# switchBoardMWS-v1.net
KiCad netlist of a schematic drawn in EAGLE
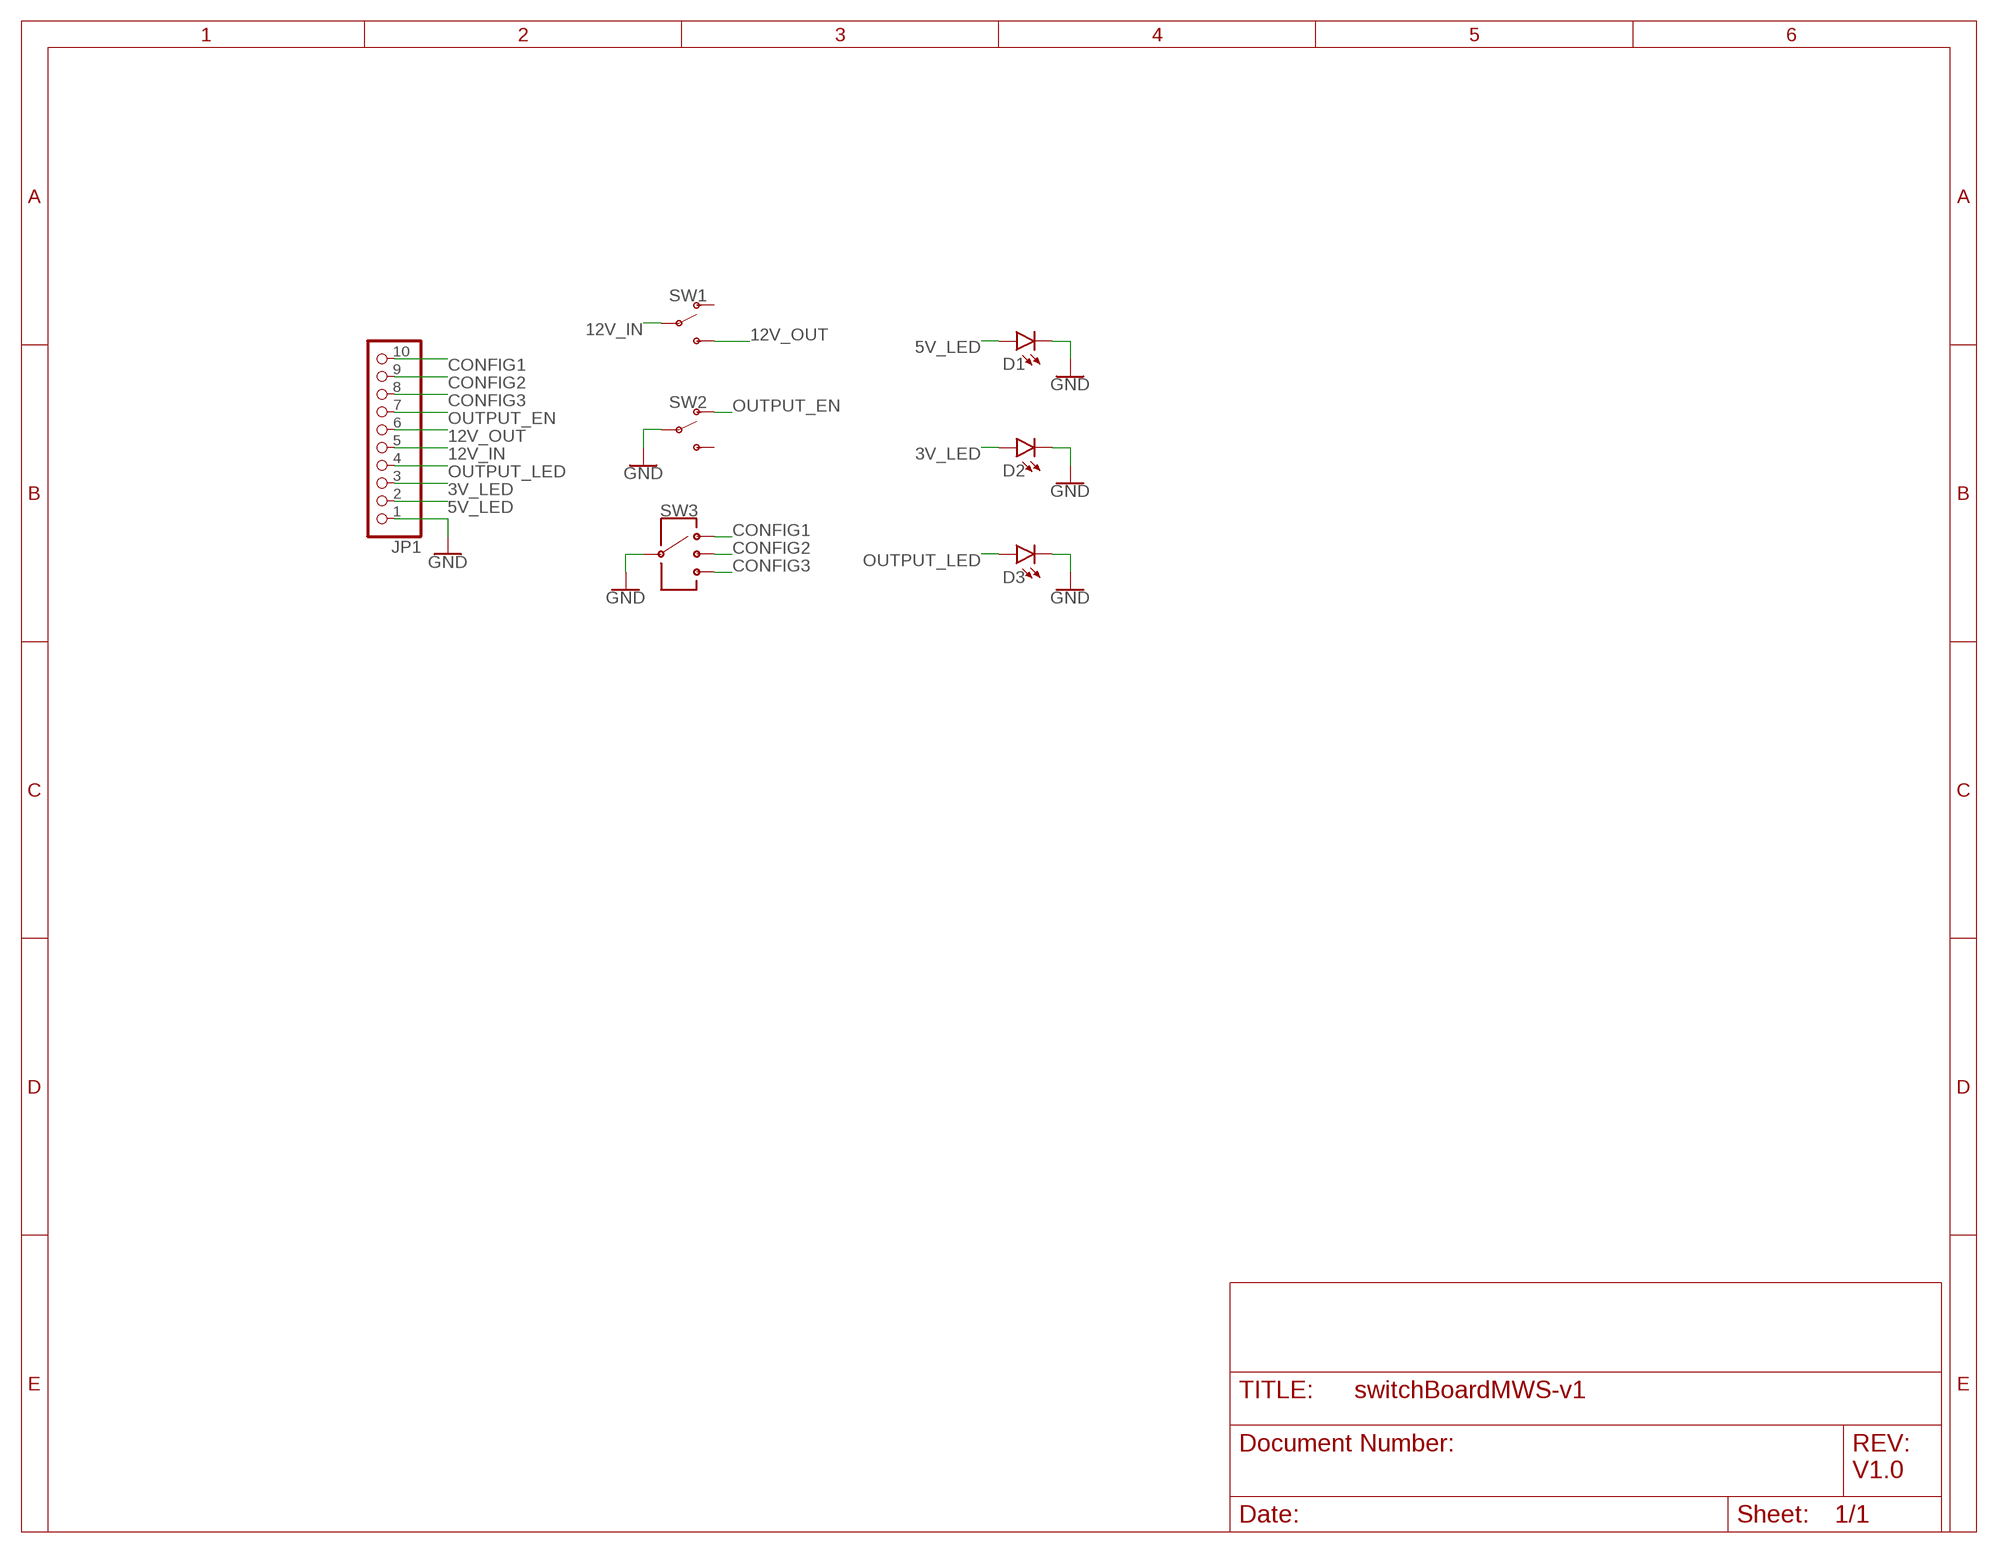
[diagram p0: schematic, sheet 1]

(export (version "E")
  (design (tool "Eeschema 10.0.6"))
  (components
    (comp (ref "D1")
      (value "LED5MM")
      (footprint "eagle-import:LED_5MM")
      (libsource (lib "eagle-import") (part "LED5MM"))
    )
    (comp (ref "D2")
      (value "LED5MM")
      (footprint "eagle-import:LED_5MM")
      (libsource (lib "eagle-import") (part "LED5MM"))
    )
    (comp (ref "D3")
      (value "LED5MM")
      (footprint "eagle-import:LED_5MM")
      (libsource (lib "eagle-import") (part "LED5MM"))
    )
    (comp (ref "JP1")
      (value "PINHD-1X10")
      (footprint "eagle-import:1X10")
      (libsource (lib "eagle-import") (part "PINHD-1X10"))
    )
    (comp (ref "SW1")
      (value "SPDT")
      (footprint "eagle-import:SPDT")
      (libsource (lib "eagle-import") (part "SPDT"))
    )
    (comp (ref "SW2")
      (value "SPDT")
      (footprint "eagle-import:SPDT")
      (libsource (lib "eagle-import") (part "SPDT"))
    )
    (comp (ref "SW3")
      (value "SP3T")
      (footprint "eagle-import:SP3T")
      (libsource (lib "eagle-import") (part "SP3T"))
    )
  )
  (nets
    (net (code "1") (name "/3V_LED") (class "Default")
      (node (ref "D2") (pin "A") (pinfunction "A_A") (pintype "passive"))
      (node (ref "JP1") (pin "3") (pinfunction "3_3") (pintype "passive"))
    )
    (net (code "2") (name "/5V_LED") (class "Default")
      (node (ref "D1") (pin "A") (pinfunction "A_A") (pintype "passive"))
      (node (ref "JP1") (pin "2") (pinfunction "2_2") (pintype "passive"))
    )
    (net (code "3") (name "/12V_IN") (class "Default")
      (node (ref "JP1") (pin "5") (pinfunction "5_5") (pintype "passive"))
      (node (ref "SW1") (pin "2") (pinfunction "P_2") (pintype "passive"))
    )
    (net (code "4") (name "/12V_OUT") (class "Default")
      (node (ref "JP1") (pin "6") (pinfunction "6_6") (pintype "passive"))
      (node (ref "SW1") (pin "3") (pinfunction "S_3") (pintype "passive"))
    )
    (net (code "5") (name "/CONFIG1") (class "Default")
      (node (ref "JP1") (pin "10") (pinfunction "10_10") (pintype "passive"))
      (node (ref "SW3") (pin "P$1") (pinfunction "1_P$1") (pintype "bidirectional"))
    )
    (net (code "6") (name "/CONFIG2") (class "Default")
      (node (ref "JP1") (pin "9") (pinfunction "9_9") (pintype "passive"))
      (node (ref "SW3") (pin "P$3") (pinfunction "3_P$3") (pintype "bidirectional"))
    )
    (net (code "7") (name "/CONFIG3") (class "Default")
      (node (ref "JP1") (pin "8") (pinfunction "8_8") (pintype "passive"))
      (node (ref "SW3") (pin "P$4") (pinfunction "4_P$4") (pintype "bidirectional"))
    )
    (net (code "8") (name "/OUTPUT_EN") (class "Default")
      (node (ref "JP1") (pin "7") (pinfunction "7_7") (pintype "passive"))
      (node (ref "SW2") (pin "1") (pinfunction "O_1") (pintype "passive"))
    )
    (net (code "9") (name "/OUTPUT_LED") (class "Default")
      (node (ref "D3") (pin "A") (pinfunction "A_A") (pintype "passive"))
      (node (ref "JP1") (pin "4") (pinfunction "4_4") (pintype "passive"))
    )
    (net (code "10") (name "GND") (class "Default")
      (node (ref "D1") (pin "K") (pinfunction "C_K") (pintype "passive"))
      (node (ref "D2") (pin "K") (pinfunction "C_K") (pintype "passive"))
      (node (ref "D3") (pin "K") (pinfunction "C_K") (pintype "passive"))
      (node (ref "JP1") (pin "1") (pinfunction "1_1") (pintype "passive"))
      (node (ref "SW2") (pin "2") (pinfunction "P_2") (pintype "passive"))
      (node (ref "SW3") (pin "P$2") (pinfunction "2_P$2") (pintype "bidirectional"))
    )
    (net (code "11") (name "unconnected-(SW1-O-Pad1)") (class "Default")
      (node (ref "SW1") (pin "1") (pinfunction "O_1") (pintype "passive"))
    )
    (net (code "12") (name "unconnected-(SW2-S-Pad3)") (class "Default")
      (node (ref "SW2") (pin "3") (pinfunction "S_3") (pintype "passive"))
    )
  )
)
